# ArduinoZeroV4_0_1.net
KiCad netlist of a schematic drawn in Altium Designer
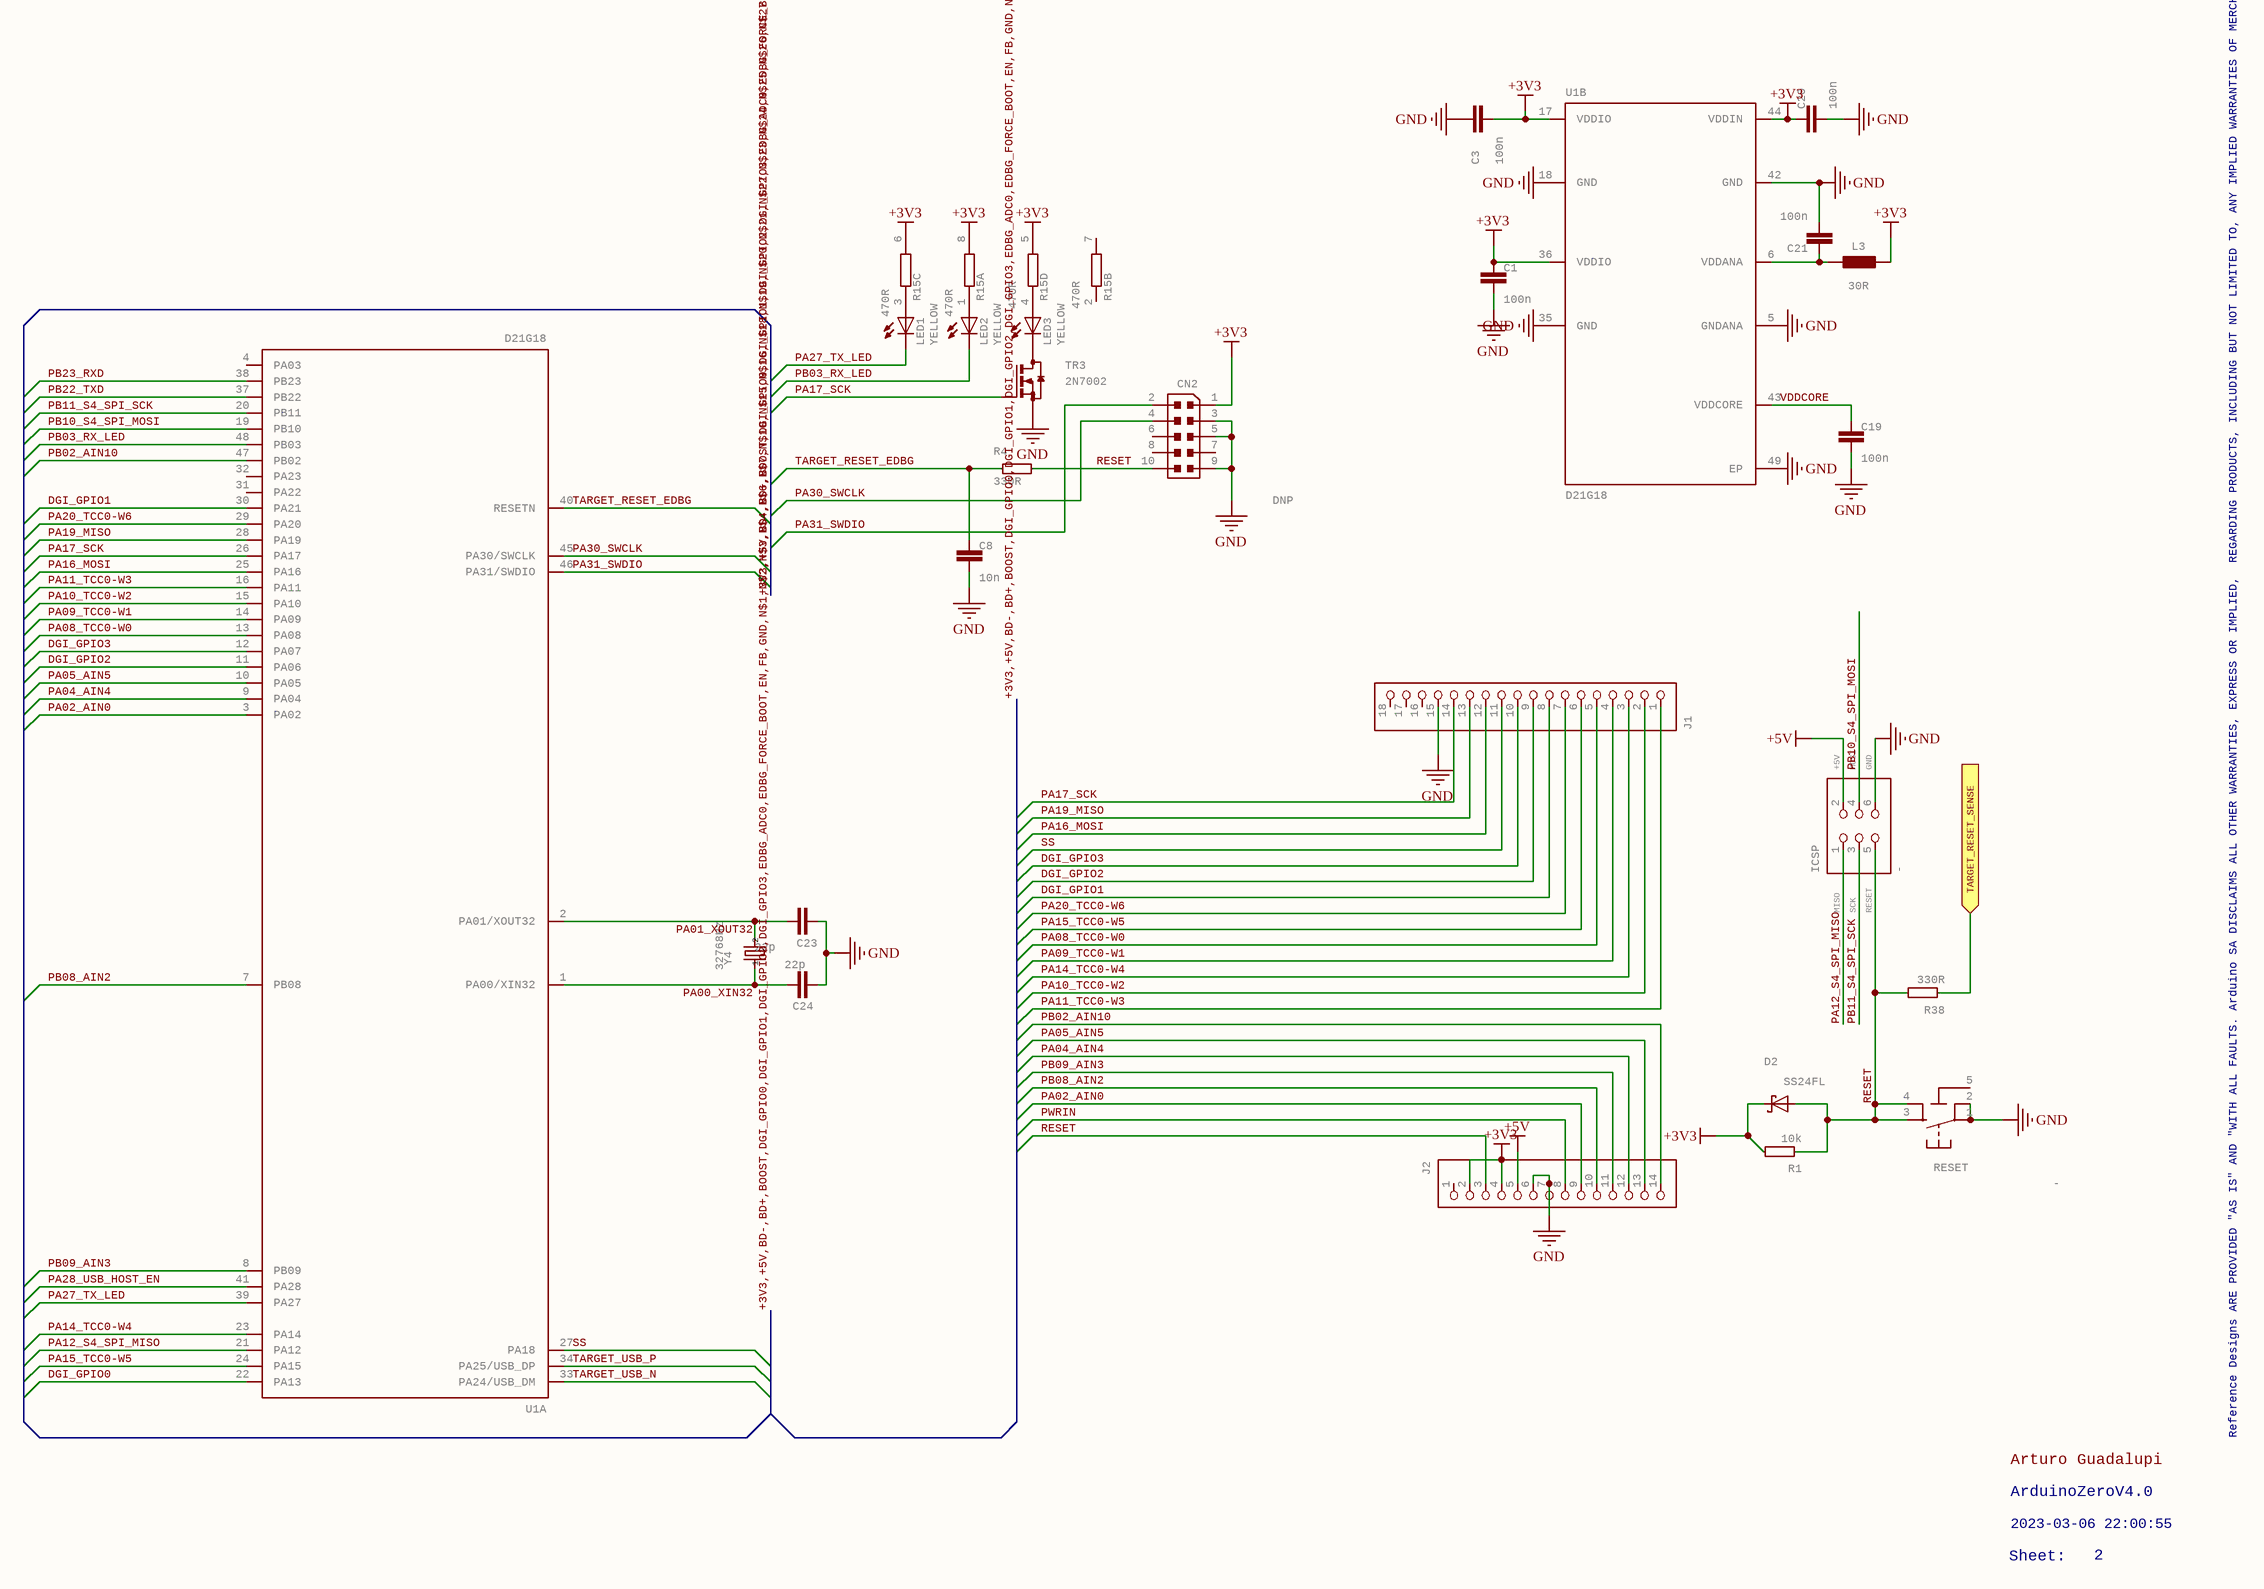
[diagram p0: ArduinoZeroV4.0_1.SchDoc]

(export (version "E")
  (design (tool "Eeschema 10.0.6"))
  (components
    (comp (ref "C1")
      (value "100n")
      (footprint "0603-1608X90N")
      (description "SMD Capacitor")
      (fields (field (name "MANUFACTURER") "Murata"))
      (libsource (lib "Arduino-rcl") (part "C-0603"))
    )
    (comp (ref "C3")
      (value "100n")
      (footprint "0603-1608X90N")
      (description "SMD Capacitor")
      (fields (field (name "MANUFACTURER") "Murata"))
      (libsource (lib "") (part "C-0603_1"))
    )
    (comp (ref "C8")
      (value "10n")
      (footprint "0603-1608X90N")
      (description "SMD Capacitor")
      (fields (field (name "MANUFACTURER") "Murata"))
      (libsource (lib "Arduino-rcl") (part "C-0603"))
    )
    (comp (ref "C19")
      (value "100n")
      (footprint "0603-1608X90N")
      (description "SMD Capacitor")
      (fields (field (name "MANUFACTURER") "Murata"))
      (libsource (lib "Arduino-rcl") (part "C-0603"))
    )
    (comp (ref "C20")
      (value "100n")
      (footprint "0603-1608X90N")
      (description "SMD Capacitor")
      (fields (field (name "MANUFACTURER") "Murata"))
      (libsource (lib "") (part "C-0603_1"))
    )
    (comp (ref "C21")
      (value "100n")
      (footprint "0603-1608X90N")
      (description "SMD Capacitor")
      (fields (field (name "MANUFACTURER") "Murata"))
      (libsource (lib "") (part "C-0603_3"))
    )
    (comp (ref "C23")
      (value "22p")
      (footprint "0603-1608X90N")
      (description "SMD Capacitor")
      (fields (field (name "MANUFACTURER") "Samsung"))
      (libsource (lib "") (part "C-0603_2"))
    )
    (comp (ref "C24")
      (value "22p")
      (footprint "0603-1608X90N")
      (description "SMD Capacitor")
      (fields (field (name "MANUFACTURER") "Samsung"))
      (libsource (lib "") (part "C-0603_2"))
    )
    (comp (ref "CN2")
      (value "DNP")
      (footprint "PINHEAD_2X05_127")
      (description "2x5 PASSO 1,27")
      (libsource (lib "Arduino-connectors") (part "JTAG_CONNECTOR-DNP"))
    )
    (comp (ref "D2")
      (value "SS24FL")
      (footprint "SOD123F")
      (description "Schottky diode")
      (fields (field (name "MANUFACTURER") "Fairchild"))
      (libsource (lib "Arduino-diodes") (part "SS24FL"))
    )
    (comp (ref "ICSP")
      (value "-")
      (footprint "2X03")
      (description "PIN HEADER")
      (fields
        (field (name "MISO") "MISO")
        (field (name "SCK") "SCK")
        (field (name "RESET") "RESET")
        (field (name "+5V") "+5V")
        (field (name "MOSI") "MOSI")
        (field (name "GND") "GND")
        (field (name "MANUFACTURER") "Adam Tech")
      )
      (libsource (lib "Arduino-connectors") (part "PINHD-2X03-ICSPTH"))
    )
    (comp (ref "J1")
      (value "-")
      (footprint "1X18-CUSTOM")
      (description "Pin header")
      (libsource (lib "Arduino-connectors") (part "PINHD-1X18-CUSTOM_OLD"))
    )
    (comp (ref "J2")
      (value "-")
      (footprint "1X14-CUSTOM")
      (description "PIN HEADER")
      (libsource (lib "Arduino-connectors") (part "PINHD-1X14-CUSTOM_OLD"))
    )
    (comp (ref "L3")
      (value "30R")
      (footprint "0805-R2013X50N")
      (description "SMD ferrite")
      (fields (field (name "MANUFACTURER") "Murata"))
      (libsource (lib "Arduino-rcl") (part "FERRITE0805"))
    )
    (comp (ref "LED1")
      (value "YELLOW")
      (footprint "CHIPLED_0805")
      (description "LED")
      (fields (field (name "MANUFACTURER") "Lite-On"))
      (libsource (lib "Arduino-diodes") (part "LED-0805"))
    )
    (comp (ref "LED2")
      (value "YELLOW")
      (footprint "CHIPLED_0805")
      (description "LED")
      (fields (field (name "MANUFACTURER") "Lite-On"))
      (libsource (lib "Arduino-diodes") (part "LED-0805"))
    )
    (comp (ref "LED3")
      (value "YELLOW")
      (footprint "CHIPLED_0805")
      (description "LED")
      (fields (field (name "MANUFACTURER") "Lite-On"))
      (libsource (lib "Arduino-diodes") (part "LED-0805"))
    )
    (comp (ref "R1")
      (value "10k")
      (footprint "C0603")
      (description "SMD Resistor")
      (fields (field (name "MANUFACTURER") "Yageo"))
      (libsource (lib "Arduino-rcl") (part "R-0603"))
    )
    (comp (ref "R4")
      (value "330R")
      (footprint "C0603")
      (description "SMD Resistor")
      (fields (field (name "MANUFACTURER") "Yageo"))
      (libsource (lib "Arduino-rcl") (part "R-0603"))
    )
    (comp (ref "R15")
      (value "470R")
      (footprint "CAY16")
      (description "Array Chip Resistor   Source: RS Component / Phycomp")
      (fields (field (name "MANUFACTURER") "Bourns Inc."))
      (libsource (lib "Arduino-rcl") (part "4R-NCAY16"))
    )
    (comp (ref "R38")
      (value "330R")
      (footprint "C0603")
      (description "SMD Resistor")
      (fields (field (name "MANUFACTURER") "Yageo"))
      (libsource (lib "Arduino-rcl") (part "R-0603"))
    )
    (comp (ref "RESET")
      (value "-")
      (footprint "TS42")
      (description "Pushbutton")
      (fields (field (name "MANUFACTURER") "TE") (field (name "LIBRARYNAME") "Arduino-pushbuttons"))
      (libsource (lib "Arduino-pushbuttons") (part "TACTILE2"))
    )
    (comp (ref "TR3")
      (value "2N7002")
      (footprint "SOT23")
      (description "MOSFET N-CH 60V 115MA")
      (fields (field (name "MANUFACTURER") "Micro Commercial Co"))
      (libsource (lib "Arduino-transistors") (part "2N7002T-SOT23"))
    )
    (comp (ref "U1")
      (value "D21G18")
      (footprint "QFN50P700X700X90-49XN-EPSQ515")
      (description "ARMÂ® CortexÂ®-M0+ SAM D21G Microcontroller IC 32-Bit 48MHz 256KB (256K x 8) FLASH 48-TQFP (7x7)")
      (fields (field (name "MANUFACTURER") "DNP") (field (name "LIBRARYNAME") "Arduino-ucs&SoCs"))
      (libsource (lib "Arduino-ucs&SoCs") (part "ATSAMD21G18A-48QFN"))
    )
    (comp (ref "Y4")
      (value "32768Hz")
      (footprint "ABS07")
      (description "LF crystal")
      (fields (field (name "1") "1") (field (name "2") "2") (field (name "MANUFACTURER") "Abracon LLC"))
      (libsource (lib "Arduino-crystals") (part "32.768KHZ"))
    )
  )
  (nets
    (net (code "2") (name "+3V3") (class "Default")
      (node (ref "C1") (pin "1") (pinfunction "1_1") (pintype "passive"))
      (node (ref "C20") (pin "1") (pinfunction "1_1") (pintype "passive"))
      (node (ref "C3") (pin "2") (pinfunction "2_2") (pintype "passive"))
      (node (ref "CN2") (pin "1") (pinfunction "1_1") (pintype "passive"))
      (node (ref "D2") (pin "C") (pinfunction "C_C") (pintype "passive"))
      (node (ref "J2") (pin "2") (pinfunction "2_2") (pintype "passive"))
      (node (ref "J2") (pin "4") (pinfunction "4_4") (pintype "passive"))
      (node (ref "L3") (pin "2") (pinfunction "2_2") (pintype "passive"))
      (node (ref "R1") (pin "2") (pinfunction "2_2") (pintype "passive"))
      (node (ref "R15") (pin "5") (pinfunction "2_5") (pintype "passive"))
      (node (ref "R15") (pin "6") (pinfunction "2_6") (pintype "passive"))
      (node (ref "R15") (pin "8") (pinfunction "2_8") (pintype "passive"))
      (node (ref "U1") (pin "17") (pinfunction "VDDIO_17") (pintype "power_in"))
      (node (ref "U1") (pin "36") (pinfunction "VDDIO_36") (pintype "power_in"))
      (node (ref "U1") (pin "44") (pinfunction "VDDIN_44") (pintype "power_in"))
    )
    (net (code "3") (name "+5V") (class "Default")
      (node (ref "ICSP") (pin "2") (pinfunction "2_2") (pintype "passive"))
      (node (ref "J2") (pin "5") (pinfunction "5_5") (pintype "passive"))
    )
    (net (code "4") (name "/DGI_GPIO0") (class "Default")
      (node (ref "U1") (pin "22") (pinfunction "PA13_22") (pintype "bidirectional"))
    )
    (net (code "5") (name "/DGI_GPIO1") (class "Default")
      (node (ref "J1") (pin "8") (pinfunction "8_8") (pintype "passive"))
      (node (ref "U1") (pin "30") (pinfunction "PA21_30") (pintype "bidirectional"))
    )
    (net (code "6") (name "/DGI_GPIO2") (class "Default")
      (node (ref "J1") (pin "9") (pinfunction "9_9") (pintype "passive"))
      (node (ref "U1") (pin "11") (pinfunction "PA06_11") (pintype "bidirectional"))
    )
    (net (code "7") (name "/DGI_GPIO3") (class "Default")
      (node (ref "J1") (pin "10") (pinfunction "10_10") (pintype "passive"))
      (node (ref "U1") (pin "12") (pinfunction "PA07_12") (pintype "bidirectional"))
    )
    (net (code "8") (name "/PA00_XIN32") (class "Default")
      (node (ref "C24") (pin "2") (pinfunction "2_2") (pintype "passive"))
      (node (ref "U1") (pin "1") (pinfunction "PA00/XIN32_1") (pintype "bidirectional"))
      (node (ref "Y4") (pin "1") (pinfunction "1_1") (pintype "passive"))
    )
    (net (code "9") (name "/PA01_XOUT32") (class "Default")
      (node (ref "C23") (pin "2") (pinfunction "2_2") (pintype "passive"))
      (node (ref "U1") (pin "2") (pinfunction "PA01/XOUT32_2") (pintype "bidirectional"))
      (node (ref "Y4") (pin "2") (pinfunction "2_2") (pintype "passive"))
    )
    (net (code "10") (name "/PA02_AIN0") (class "Default")
      (node (ref "J2") (pin "9") (pinfunction "9_9") (pintype "passive"))
      (node (ref "U1") (pin "3") (pinfunction "PA02_3") (pintype "bidirectional"))
    )
    (net (code "11") (name "/PA04_AIN4") (class "Default")
      (node (ref "J2") (pin "12") (pinfunction "12_12") (pintype "passive"))
      (node (ref "U1") (pin "9") (pinfunction "PA04_9") (pintype "bidirectional"))
    )
    (net (code "12") (name "/PA05_AIN5") (class "Default")
      (node (ref "J2") (pin "13") (pinfunction "13_13") (pintype "passive"))
      (node (ref "U1") (pin "10") (pinfunction "PA05_10") (pintype "bidirectional"))
    )
    (net (code "13") (name "/PA08_TCC0-W0") (class "Default")
      (node (ref "J1") (pin "5") (pinfunction "5_5") (pintype "passive"))
      (node (ref "U1") (pin "13") (pinfunction "PA08_13") (pintype "bidirectional"))
    )
    (net (code "14") (name "/PA09_TCC0-W1") (class "Default")
      (node (ref "J1") (pin "4") (pinfunction "4_4") (pintype "passive"))
      (node (ref "U1") (pin "14") (pinfunction "PA09_14") (pintype "bidirectional"))
    )
    (net (code "15") (name "/PA10_TCC0-W2") (class "Default")
      (node (ref "J1") (pin "2") (pinfunction "2_2") (pintype "passive"))
      (node (ref "U1") (pin "15") (pinfunction "PA10_15") (pintype "bidirectional"))
    )
    (net (code "16") (name "/PA11_TCC0-W3") (class "Default")
      (node (ref "J1") (pin "1") (pinfunction "1_1") (pintype "passive"))
      (node (ref "U1") (pin "16") (pinfunction "PA11_16") (pintype "bidirectional"))
    )
    (net (code "17") (name "/PA12_S4_SPI_MISO") (class "Default")
      (node (ref "ICSP") (pin "1") (pinfunction "1_1") (pintype "passive"))
      (node (ref "U1") (pin "21") (pinfunction "PA12_21") (pintype "bidirectional"))
    )
    (net (code "18") (name "/PA14_TCC0-W4") (class "Default")
      (node (ref "J1") (pin "3") (pinfunction "3_3") (pintype "passive"))
      (node (ref "U1") (pin "23") (pinfunction "PA14_23") (pintype "bidirectional"))
    )
    (net (code "19") (name "/PA15_TCC0-W5") (class "Default")
      (node (ref "J1") (pin "6") (pinfunction "6_6") (pintype "passive"))
      (node (ref "U1") (pin "24") (pinfunction "PA15_24") (pintype "bidirectional"))
    )
    (net (code "20") (name "/PA16_MOSI") (class "Default")
      (node (ref "J1") (pin "12") (pinfunction "12_12") (pintype "passive"))
      (node (ref "U1") (pin "25") (pinfunction "PA16_25") (pintype "bidirectional"))
    )
    (net (code "21") (name "/PA17_SCK") (class "Default")
      (node (ref "J1") (pin "14") (pinfunction "14_14") (pintype "passive"))
      (node (ref "TR3") (pin "1") (pinfunction "G_1") (pintype "passive"))
      (node (ref "U1") (pin "26") (pinfunction "PA17_26") (pintype "bidirectional"))
    )
    (net (code "22") (name "/PA19_MISO") (class "Default")
      (node (ref "J1") (pin "13") (pinfunction "13_13") (pintype "passive"))
      (node (ref "U1") (pin "28") (pinfunction "PA19_28") (pintype "bidirectional"))
    )
    (net (code "23") (name "/PA20_TCC0-W6") (class "Default")
      (node (ref "J1") (pin "7") (pinfunction "7_7") (pintype "passive"))
      (node (ref "U1") (pin "29") (pinfunction "PA20_29") (pintype "bidirectional"))
    )
    (net (code "24") (name "/PA27_TX_LED") (class "Default")
      (node (ref "LED1") (pin "C") (pinfunction "C_C") (pintype "passive"))
      (node (ref "U1") (pin "39") (pinfunction "PA27_39") (pintype "bidirectional"))
    )
    (net (code "25") (name "/PA28_USB_HOST_EN") (class "Default")
      (node (ref "U1") (pin "41") (pinfunction "PA28_41") (pintype "bidirectional"))
    )
    (net (code "26") (name "/PA30_SWCLK") (class "Default")
      (node (ref "CN2") (pin "4") (pinfunction "4_4") (pintype "passive"))
      (node (ref "U1") (pin "45") (pinfunction "PA30/SWCLK_45") (pintype "bidirectional"))
    )
    (net (code "27") (name "/PA31_SWDIO") (class "Default")
      (node (ref "CN2") (pin "2") (pinfunction "2_2") (pintype "passive"))
      (node (ref "U1") (pin "46") (pinfunction "PA31/SWDIO_46") (pintype "bidirectional"))
    )
    (net (code "28") (name "/PB02_AIN10") (class "Default")
      (node (ref "J2") (pin "14") (pinfunction "14_14") (pintype "passive"))
      (node (ref "U1") (pin "47") (pinfunction "PB02_47") (pintype "bidirectional"))
    )
    (net (code "29") (name "/PB03_RX_LED") (class "Default")
      (node (ref "LED2") (pin "C") (pinfunction "C_C") (pintype "passive"))
      (node (ref "U1") (pin "48") (pinfunction "PB03_48") (pintype "bidirectional"))
    )
    (net (code "30") (name "/PB08_AIN2") (class "Default")
      (node (ref "J2") (pin "10") (pinfunction "10_10") (pintype "passive"))
      (node (ref "U1") (pin "7") (pinfunction "PB08_7") (pintype "bidirectional"))
    )
    (net (code "31") (name "/PB09_AIN3") (class "Default")
      (node (ref "J2") (pin "11") (pinfunction "11_11") (pintype "passive"))
      (node (ref "U1") (pin "8") (pinfunction "PB09_8") (pintype "bidirectional"))
    )
    (net (code "32") (name "/PB10_S4_SPI_MOSI") (class "Default")
      (node (ref "ICSP") (pin "4") (pinfunction "4_4") (pintype "passive"))
      (node (ref "U1") (pin "19") (pinfunction "PB10_19") (pintype "bidirectional"))
    )
    (net (code "33") (name "/PB11_S4_SPI_SCK") (class "Default")
      (node (ref "ICSP") (pin "3") (pinfunction "3_3") (pintype "passive"))
      (node (ref "U1") (pin "20") (pinfunction "PB11_20") (pintype "bidirectional"))
    )
    (net (code "34") (name "/PB22_TXD") (class "Default")
      (node (ref "U1") (pin "37") (pinfunction "PB22_37") (pintype "bidirectional"))
    )
    (net (code "35") (name "/PB23_RXD") (class "Default")
      (node (ref "U1") (pin "38") (pinfunction "PB23_38") (pintype "bidirectional"))
    )
    (net (code "36") (name "/PWRIN") (class "Default")
      (node (ref "J2") (pin "8") (pinfunction "8_8") (pintype "passive"))
    )
    (net (code "37") (name "/RESET") (class "Default")
      (node (ref "CN2") (pin "10") (pinfunction "10_10") (pintype "passive"))
      (node (ref "D2") (pin "A") (pinfunction "A_A") (pintype "passive"))
      (node (ref "ICSP") (pin "5") (pinfunction "5_5") (pintype "passive"))
      (node (ref "J2") (pin "3") (pinfunction "3_3") (pintype "passive"))
      (node (ref "R1") (pin "1") (pinfunction "1_1") (pintype "passive"))
      (node (ref "R38") (pin "2") (pinfunction "2_2") (pintype "passive"))
      (node (ref "R4") (pin "2") (pinfunction "2_2") (pintype "passive"))
      (node (ref "RESET") (pin "3") (pinfunction "3_3") (pintype "passive"))
      (node (ref "RESET") (pin "4") (pinfunction "4_4") (pintype "passive"))
    )
    (net (code "38") (name "/SS") (class "Default")
      (node (ref "J1") (pin "11") (pinfunction "11_11") (pintype "passive"))
      (node (ref "U1") (pin "27") (pinfunction "PA18_27") (pintype "bidirectional"))
    )
    (net (code "39") (name "/TARGET_RESET_EDBG") (class "Default")
      (node (ref "C8") (pin "1") (pinfunction "1_1") (pintype "passive"))
      (node (ref "R4") (pin "1") (pinfunction "1_1") (pintype "passive"))
      (node (ref "U1") (pin "40") (pinfunction "RESETN_40") (pintype "bidirectional"))
    )
    (net (code "40") (name "/TARGET_RESET_SENSE") (class "Default")
      (node (ref "R38") (pin "1") (pinfunction "1_1") (pintype "passive"))
    )
    (net (code "41") (name "/TARGET_USB_N") (class "Default")
      (node (ref "U1") (pin "33") (pinfunction "PA24/USB_DM_33") (pintype "bidirectional"))
    )
    (net (code "42") (name "/TARGET_USB_P") (class "Default")
      (node (ref "U1") (pin "34") (pinfunction "PA25/USB_DP_34") (pintype "bidirectional"))
    )
    (net (code "43") (name "/VDDCORE") (class "Default")
      (node (ref "C19") (pin "1") (pinfunction "1_1") (pintype "passive"))
      (node (ref "U1") (pin "43") (pinfunction "VDDCORE_43") (pintype "power_in"))
    )
    (net (code "45") (name "GND") (class "Default")
      (node (ref "C1") (pin "2") (pinfunction "2_2") (pintype "passive"))
      (node (ref "C19") (pin "2") (pinfunction "2_2") (pintype "passive"))
      (node (ref "C20") (pin "2") (pinfunction "2_2") (pintype "passive"))
      (node (ref "C21") (pin "2") (pinfunction "2_2") (pintype "passive"))
      (node (ref "C23") (pin "1") (pinfunction "1_1") (pintype "passive"))
      (node (ref "C24") (pin "1") (pinfunction "1_1") (pintype "passive"))
      (node (ref "C3") (pin "1") (pinfunction "1_1") (pintype "passive"))
      (node (ref "C8") (pin "2") (pinfunction "2_2") (pintype "passive"))
      (node (ref "CN2") (pin "3") (pinfunction "3_3") (pintype "passive"))
      (node (ref "CN2") (pin "5") (pinfunction "5_5") (pintype "passive"))
      (node (ref "CN2") (pin "9") (pinfunction "9_9") (pintype "passive"))
      (node (ref "ICSP") (pin "6") (pinfunction "6_6") (pintype "passive"))
      (node (ref "J1") (pin "15") (pinfunction "15_15") (pintype "passive"))
      (node (ref "J2") (pin "6") (pinfunction "6_6") (pintype "passive"))
      (node (ref "J2") (pin "7") (pinfunction "7_7") (pintype "passive"))
      (node (ref "RESET") (pin "1") (pinfunction "1_1") (pintype "passive"))
      (node (ref "RESET") (pin "2") (pinfunction "2_2") (pintype "passive"))
      (node (ref "TR3") (pin "2") (pinfunction "S_2") (pintype "passive"))
      (node (ref "U1") (pin "18") (pinfunction "GND_18") (pintype "power_in"))
      (node (ref "U1") (pin "35") (pinfunction "GND_35") (pintype "power_in"))
      (node (ref "U1") (pin "42") (pinfunction "GND_42") (pintype "power_in"))
      (node (ref "U1") (pin "49") (pinfunction "EP_49") (pintype "passive"))
      (node (ref "U1") (pin "5") (pinfunction "GNDANA_5") (pintype "power_in"))
    )
    (net (code "46") (name "Net-(LED2-PadA)") (class "Default")
      (node (ref "LED2") (pin "A") (pinfunction "A_A") (pintype "passive"))
      (node (ref "R15") (pin "1") (pinfunction "1_1") (pintype "passive"))
    )
    (net (code "47") (name "Net-(R15C-1)") (class "Default")
      (node (ref "LED1") (pin "A") (pinfunction "A_A") (pintype "passive"))
      (node (ref "R15") (pin "3") (pinfunction "1_3") (pintype "passive"))
    )
    (net (code "48") (name "Net-(R15D-1)") (class "Default")
      (node (ref "LED3") (pin "A") (pinfunction "A_A") (pintype "passive"))
      (node (ref "R15") (pin "4") (pinfunction "1_4") (pintype "passive"))
    )
    (net (code "49") (name "Net-(TR3-D)") (class "Default")
      (node (ref "LED3") (pin "C") (pinfunction "C_C") (pintype "passive"))
      (node (ref "TR3") (pin "3") (pinfunction "D_3") (pintype "passive"))
    )
    (net (code "50") (name "Net-(U1B-VDDANA)") (class "Default")
      (node (ref "C21") (pin "1") (pinfunction "1_1") (pintype "passive"))
      (node (ref "L3") (pin "1") (pinfunction "1_1") (pintype "passive"))
      (node (ref "U1") (pin "6") (pinfunction "VDDANA_6") (pintype "power_in"))
    )
    (net (code "51") (name "unconnected-(CN2-Pad6)") (class "Default")
      (node (ref "CN2") (pin "6") (pinfunction "6_6") (pintype "passive"))
    )
    (net (code "52") (name "unconnected-(CN2-Pad7)") (class "Default")
      (node (ref "CN2") (pin "7") (pinfunction "7_7") (pintype "passive"))
    )
    (net (code "53") (name "unconnected-(CN2-Pad8)") (class "Default")
      (node (ref "CN2") (pin "8") (pinfunction "8_8") (pintype "passive"))
    )
    (net (code "54") (name "unconnected-(J1-Pad16)") (class "Default")
      (node (ref "J1") (pin "16") (pinfunction "16_16") (pintype "passive"))
    )
    (net (code "55") (name "unconnected-(J1-Pad17)") (class "Default")
      (node (ref "J1") (pin "17") (pinfunction "17_17") (pintype "passive"))
    )
    (net (code "56") (name "unconnected-(J1-Pad18)") (class "Default")
      (node (ref "J1") (pin "18") (pinfunction "18_18") (pintype "passive"))
    )
    (net (code "57") (name "unconnected-(J2-Pad1)") (class "Default")
      (node (ref "J2") (pin "1") (pinfunction "1_1") (pintype "passive"))
    )
    (net (code "58") (name "unconnected-(R15B-1-Pad2)") (class "Default")
      (node (ref "R15") (pin "2") (pinfunction "1_2") (pintype "passive"))
    )
    (net (code "59") (name "unconnected-(R15B-2-Pad7)") (class "Default")
      (node (ref "R15") (pin "7") (pinfunction "2_7") (pintype "passive"))
    )
    (net (code "60") (name "unconnected-(RESET-5-GND-Pad5)") (class "Default")
      (node (ref "RESET") (pin "5") (pinfunction "5-GND_5") (pintype "power_in"))
    )
    (net (code "61") (name "unconnected-(U1A-PA03-Pad4)") (class "Default")
      (node (ref "U1") (pin "4") (pinfunction "PA03_4") (pintype "bidirectional"))
    )
    (net (code "62") (name "unconnected-(U1A-PA22-Pad31)") (class "Default")
      (node (ref "U1") (pin "31") (pinfunction "PA22_31") (pintype "bidirectional"))
    )
    (net (code "63") (name "unconnected-(U1A-PA23-Pad32)") (class "Default")
      (node (ref "U1") (pin "32") (pinfunction "PA23_32") (pintype "bidirectional"))
    )
  )
)
